# treat-dispenser.net
KiCad netlist of a schematic drawn in EAGLE
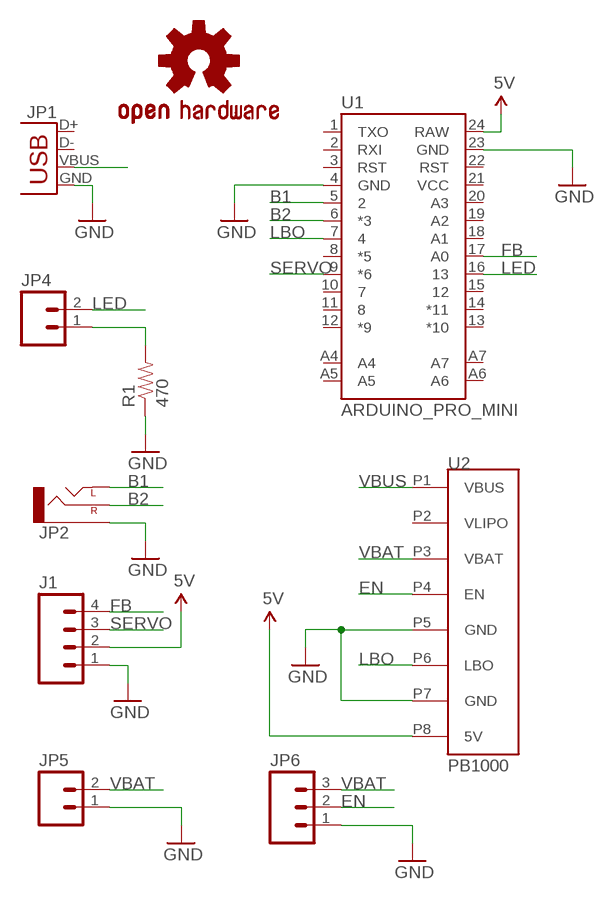
[diagram p0: schematic, sheet 1]

(export (version "E")
  (design (tool "Eeschema 10.0.6"))
  (components
    (comp (ref "J1")
      (value "M04PTH")
      (footprint "eagle-import:1X04")
      (libsource (lib "eagle-import") (part "M04PTH"))
    )
    (comp (ref "JP1")
      (value "USB-MB-H")
      (footprint "eagle-import:USB-MB-H")
      (libsource (lib "eagle-import") (part "USB-MB-H"))
    )
    (comp (ref "JP2")
      (value "AUDIO-JACKPTH")
      (footprint "eagle-import:AUDIO-JACK")
      (libsource (lib "eagle-import") (part "AUDIO-JACKPTH"))
    )
    (comp (ref "JP4")
      (value "M02PTH")
      (footprint "eagle-import:1X02")
      (libsource (lib "eagle-import") (part "M02PTH"))
    )
    (comp (ref "JP5")
      (value "M02JST-PTH-2")
      (footprint "eagle-import:JST-2-PTH")
      (libsource (lib "eagle-import") (part "M02JST-PTH-2"))
    )
    (comp (ref "JP6")
      (value "M03PTH")
      (footprint "eagle-import:1X03")
      (libsource (lib "eagle-import") (part "M03PTH"))
    )
    (comp (ref "LOGO1")
      (value "OSHW-LOGOS")
      (footprint "eagle-import:OSHW-LOGO-S")
      (libsource (lib "eagle-import") (part "OSHW-LOGOS"))
    )
    (comp (ref "R1")
      (value "470")
      (footprint "eagle-import:AXIAL-0.4")
      (libsource (lib "eagle-import") (part "RESISTORPTH-1/4W"))
    )
    (comp (ref "U1")
      (value "ARDUINO_PRO_MINI")
      (footprint "eagle-import:ARDUINO_PRO_MINI")
      (libsource (lib "eagle-import") (part "ARDUINO_PRO_MINI"))
    )
    (comp (ref "U2")
      (value "PB1000")
      (footprint "eagle-import:PB1000")
      (libsource (lib "eagle-import") (part "PB1000"))
    )
  )
  (nets
    (net (code "1") (name "/B1") (class "Default")
      (node (ref "JP2") (pin "TIP") (pinfunction "LEFT_TIP") (pintype "bidirectional"))
      (node (ref "U1") (pin "5") (pinfunction "2_5") (pintype "bidirectional"))
    )
    (net (code "2") (name "/B2") (class "Default")
      (node (ref "JP2") (pin "RING") (pinfunction "RIGHT_RING") (pintype "bidirectional"))
      (node (ref "U1") (pin "6") (pinfunction "*3_6") (pintype "bidirectional"))
    )
    (net (code "3") (name "/EN") (class "Default")
      (node (ref "JP6") (pin "2") (pinfunction "2_2") (pintype "passive"))
      (node (ref "U2") (pin "P4") (pinfunction "EN_P4") (pintype "bidirectional"))
    )
    (net (code "4") (name "/FB") (class "Default")
      (node (ref "J1") (pin "4") (pinfunction "4_4") (pintype "passive"))
      (node (ref "U1") (pin "17") (pinfunction "A0_17") (pintype "bidirectional"))
    )
    (net (code "5") (name "/LBO") (class "Default")
      (node (ref "U1") (pin "7") (pinfunction "4_7") (pintype "bidirectional"))
      (node (ref "U2") (pin "P6") (pinfunction "LBO_P6") (pintype "bidirectional"))
    )
    (net (code "6") (name "/LED") (class "Default")
      (node (ref "JP4") (pin "2") (pinfunction "2_2") (pintype "passive"))
      (node (ref "U1") (pin "16") (pinfunction "13_16") (pintype "bidirectional"))
    )
    (net (code "7") (name "/SERVO") (class "Default")
      (node (ref "J1") (pin "3") (pinfunction "3_3") (pintype "passive"))
      (node (ref "U1") (pin "9") (pinfunction "*6_9") (pintype "bidirectional"))
    )
    (net (code "8") (name "/VBAT") (class "Default")
      (node (ref "JP5") (pin "2") (pinfunction "2_2") (pintype "passive"))
      (node (ref "JP6") (pin "3") (pinfunction "3_3") (pintype "passive"))
      (node (ref "U2") (pin "P3") (pinfunction "VBAT_P3") (pintype "bidirectional"))
    )
    (net (code "9") (name "/VBUS") (class "Default")
      (node (ref "JP1") (pin "VBUS") (pinfunction "VBUS_VBUS") (pintype "bidirectional"))
      (node (ref "U2") (pin "P1") (pinfunction "VBUS_P1") (pintype "bidirectional"))
    )
    (net (code "10") (name "5V") (class "Default")
      (node (ref "J1") (pin "2") (pinfunction "2_2") (pintype "passive"))
      (node (ref "U1") (pin "24") (pinfunction "RAW_24") (pintype "bidirectional"))
      (node (ref "U2") (pin "P8") (pinfunction "5V_P8") (pintype "bidirectional"))
    )
    (net (code "11") (name "GND") (class "Default")
      (node (ref "J1") (pin "1") (pinfunction "1_1") (pintype "passive"))
      (node (ref "JP1") (pin "GND") (pinfunction "GND_GND") (pintype "bidirectional"))
      (node (ref "JP2") (pin "SLEEVE") (pinfunction "SLEEVE_SLEEVE") (pintype "bidirectional"))
      (node (ref "JP5") (pin "1") (pinfunction "1_1") (pintype "passive"))
      (node (ref "JP6") (pin "1") (pinfunction "1_1") (pintype "passive"))
      (node (ref "R1") (pin "P$1") (pinfunction "1_P$1") (pintype "passive"))
      (node (ref "U1") (pin "23") (pinfunction "GND_23") (pintype "bidirectional"))
      (node (ref "U1") (pin "4") (pinfunction "GND_4") (pintype "bidirectional"))
      (node (ref "U2") (pin "P5") (pinfunction "GND_P5") (pintype "bidirectional"))
      (node (ref "U2") (pin "P7") (pinfunction "GND_P7") (pintype "bidirectional"))
    )
    (net (code "12") (name "Net-(R1-2)") (class "Default")
      (node (ref "JP4") (pin "1") (pinfunction "1_1") (pintype "passive"))
      (node (ref "R1") (pin "P$2") (pinfunction "2_P$2") (pintype "passive"))
    )
    (net (code "13") (name "unconnected-(JP1-PadD+)") (class "Default")
      (node (ref "JP1") (pin "D+") (pinfunction "D+_D+") (pintype "bidirectional"))
    )
    (net (code "14") (name "unconnected-(JP1-PadD-)") (class "Default")
      (node (ref "JP1") (pin "D-") (pinfunction "D-_D-") (pintype "bidirectional"))
    )
    (net (code "15") (name "unconnected-(U1-*5-Pad8)") (class "Default")
      (node (ref "U1") (pin "8") (pinfunction "*5_8") (pintype "bidirectional"))
    )
    (net (code "16") (name "unconnected-(U1-*9-Pad12)") (class "Default")
      (node (ref "U1") (pin "12") (pinfunction "*9_12") (pintype "bidirectional"))
    )
    (net (code "17") (name "unconnected-(U1-*10-Pad13)") (class "Default")
      (node (ref "U1") (pin "13") (pinfunction "*10_13") (pintype "bidirectional"))
    )
    (net (code "18") (name "unconnected-(U1-*11-Pad14)") (class "Default")
      (node (ref "U1") (pin "14") (pinfunction "*11_14") (pintype "bidirectional"))
    )
    (net (code "19") (name "unconnected-(U1-7-Pad10)") (class "Default")
      (node (ref "U1") (pin "10") (pinfunction "7_10") (pintype "bidirectional"))
    )
    (net (code "20") (name "unconnected-(U1-8-Pad11)") (class "Default")
      (node (ref "U1") (pin "11") (pinfunction "8_11") (pintype "bidirectional"))
    )
    (net (code "21") (name "unconnected-(U1-12-Pad15)") (class "Default")
      (node (ref "U1") (pin "15") (pinfunction "12_15") (pintype "bidirectional"))
    )
    (net (code "22") (name "unconnected-(U1-A1-Pad18)") (class "Default")
      (node (ref "U1") (pin "18") (pinfunction "A1_18") (pintype "bidirectional"))
    )
    (net (code "23") (name "unconnected-(U1-A2-Pad19)") (class "Default")
      (node (ref "U1") (pin "19") (pinfunction "A2_19") (pintype "bidirectional"))
    )
    (net (code "24") (name "unconnected-(U1-A3-Pad20)") (class "Default")
      (node (ref "U1") (pin "20") (pinfunction "A3_20") (pintype "bidirectional"))
    )
    (net (code "25") (name "unconnected-(U1-PadA4)") (class "Default")
      (node (ref "U1") (pin "A4") (pinfunction "A4_A4") (pintype "bidirectional"))
    )
    (net (code "26") (name "unconnected-(U1-PadA5)") (class "Default")
      (node (ref "U1") (pin "A5") (pinfunction "A5_A5") (pintype "bidirectional"))
    )
    (net (code "27") (name "unconnected-(U1-PadA6)") (class "Default")
      (node (ref "U1") (pin "A6") (pinfunction "A6_A6") (pintype "bidirectional"))
    )
    (net (code "28") (name "unconnected-(U1-PadA7)") (class "Default")
      (node (ref "U1") (pin "A7") (pinfunction "A7_A7") (pintype "bidirectional"))
    )
    (net (code "29") (name "unconnected-(U1-RST-Pad3)") (class "Default")
      (node (ref "U1") (pin "3") (pinfunction "RST_3") (pintype "bidirectional"))
    )
    (net (code "30") (name "unconnected-(U1-RST-Pad22)") (class "Default")
      (node (ref "U1") (pin "22") (pinfunction "RST_22") (pintype "bidirectional"))
    )
    (net (code "31") (name "unconnected-(U1-RXI-Pad2)") (class "Default")
      (node (ref "U1") (pin "2") (pinfunction "RXI_2") (pintype "bidirectional"))
    )
    (net (code "32") (name "unconnected-(U1-TXO-Pad1)") (class "Default")
      (node (ref "U1") (pin "1") (pinfunction "TXO_1") (pintype "bidirectional"))
    )
    (net (code "33") (name "unconnected-(U1-VCC-Pad21)") (class "Default")
      (node (ref "U1") (pin "21") (pinfunction "VCC_21") (pintype "bidirectional"))
    )
    (net (code "34") (name "unconnected-(U2-VLIPO-PadP2)") (class "Default")
      (node (ref "U2") (pin "P2") (pinfunction "VLIPO_P2") (pintype "bidirectional"))
    )
  )
)
